# Sheet1.net
KiCad netlist of a schematic drawn in Altium Designer
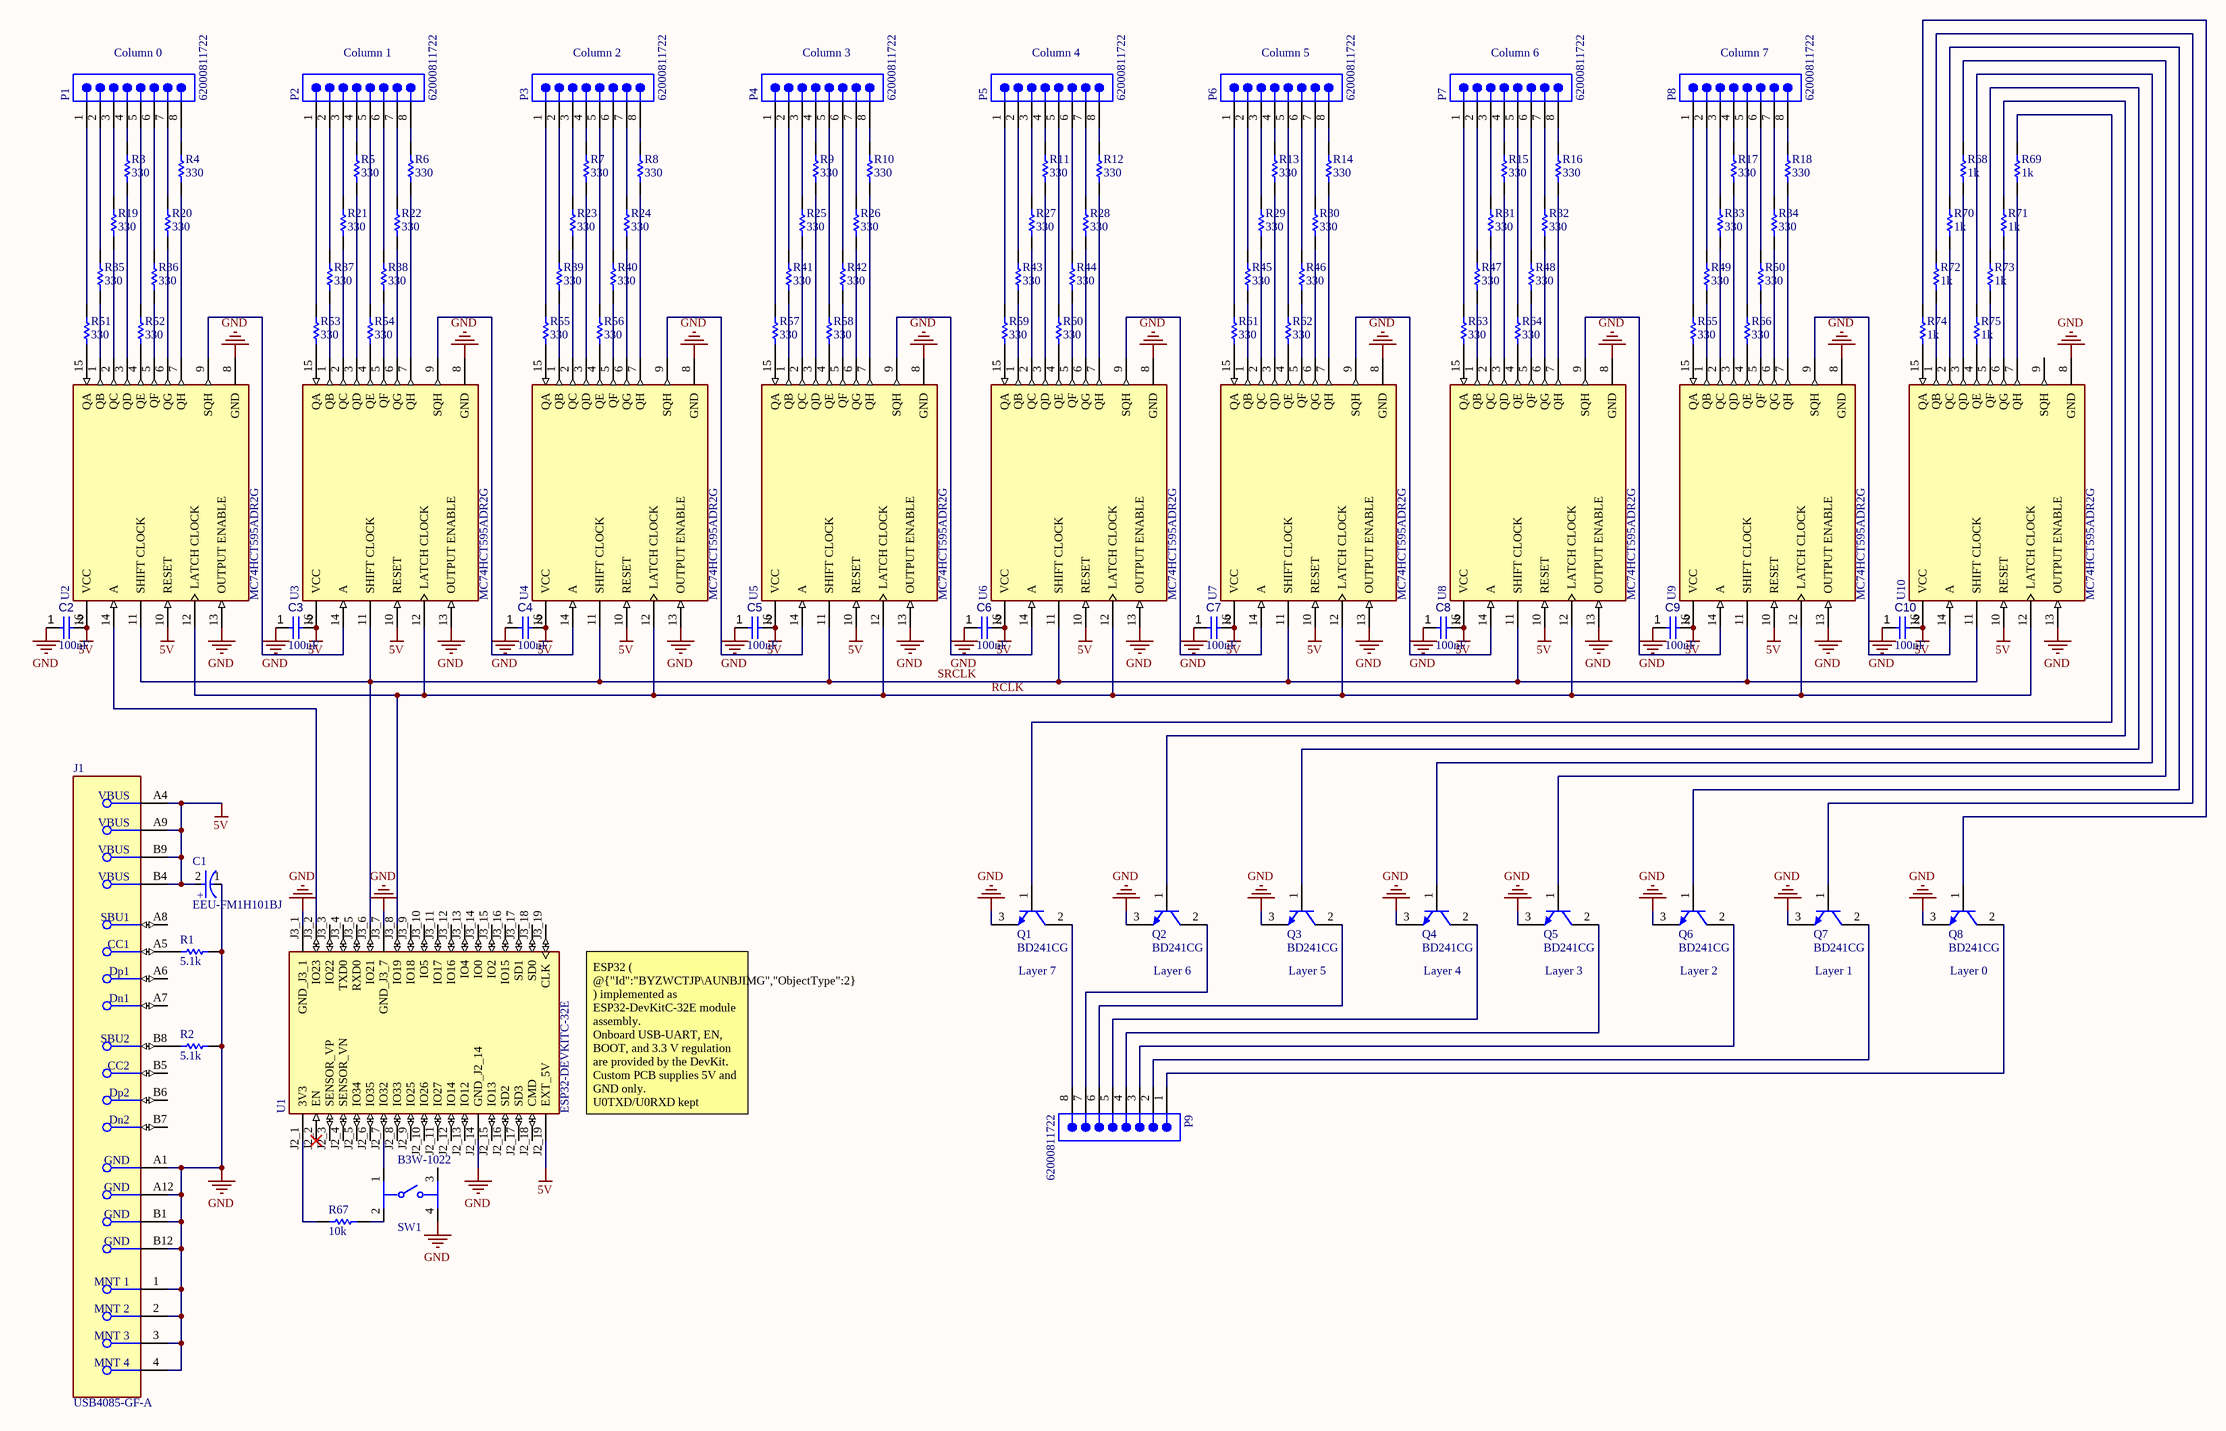
[diagram p0: Sheet1.SchDoc]

(export (version "E")
  (design (tool "Eeschema 10.0.6"))
  (components
    (comp (ref "C1")
      (value "EEU-FM1H101BJ")
      (footprint "FP-FM8-MFG")
      (description "CAP ALUM 100UF 20% 50V RADIAL")
      (fields (field (name "TOLERANCE") "20%"))
      (libsource (lib "Altium Content Vault") (part "203bc49f2ac43e59fd269a8c329ed05"))
    )
    (comp (ref "C2")
      (value "100nF")
      (footprint "CAPC0402(1005)60_L")
      (description "Chip Capacitor, 100nF +/-20%, 25V, 0402, Thickness 0.6 mm")
      (fields (field (name "TOLERANCE") "10%") (field (name "Comment") "Capacitor 100nF +/-20% 25V 0402"))
      (libsource (lib "nikita juscenko") (part "CAP-NP-2"))
    )
    (comp (ref "C3")
      (value "100nF")
      (footprint "CAPC0402(1005)60_L")
      (description "Chip Capacitor, 100nF +/-20%, 25V, 0402, Thickness 0.6 mm")
      (fields (field (name "TOLERANCE") "10%") (field (name "Comment") "Capacitor 100nF +/-20% 25V 0402"))
      (libsource (lib "nikita juscenko") (part "CAP-NP-2"))
    )
    (comp (ref "C4")
      (value "100nF")
      (footprint "CAPC0402(1005)60_L")
      (description "Chip Capacitor, 100nF +/-20%, 25V, 0402, Thickness 0.6 mm")
      (fields (field (name "TOLERANCE") "10%") (field (name "Comment") "Capacitor 100nF +/-20% 25V 0402"))
      (libsource (lib "nikita juscenko") (part "CAP-NP-2"))
    )
    (comp (ref "C5")
      (value "100nF")
      (footprint "CAPC0402(1005)60_L")
      (description "Chip Capacitor, 100nF +/-20%, 25V, 0402, Thickness 0.6 mm")
      (fields (field (name "TOLERANCE") "10%") (field (name "Comment") "Capacitor 100nF +/-20% 25V 0402"))
      (libsource (lib "nikita juscenko") (part "CAP-NP-2"))
    )
    (comp (ref "C6")
      (value "100nF")
      (footprint "CAPC0402(1005)60_L")
      (description "Chip Capacitor, 100nF +/-20%, 25V, 0402, Thickness 0.6 mm")
      (fields (field (name "TOLERANCE") "10%") (field (name "Comment") "Capacitor 100nF +/-20% 25V 0402"))
      (libsource (lib "nikita juscenko") (part "CAP-NP-2"))
    )
    (comp (ref "C7")
      (value "100nF")
      (footprint "CAPC0402(1005)60_L")
      (description "Chip Capacitor, 100nF +/-20%, 25V, 0402, Thickness 0.6 mm")
      (fields (field (name "TOLERANCE") "10%") (field (name "Comment") "Capacitor 100nF +/-20% 25V 0402"))
      (libsource (lib "nikita juscenko") (part "CAP-NP-2"))
    )
    (comp (ref "C8")
      (value "100nF")
      (footprint "CAPC0402(1005)60_L")
      (description "Chip Capacitor, 100nF +/-20%, 25V, 0402, Thickness 0.6 mm")
      (fields (field (name "TOLERANCE") "10%") (field (name "Comment") "Capacitor 100nF +/-20% 25V 0402"))
      (libsource (lib "nikita juscenko") (part "CAP-NP-2"))
    )
    (comp (ref "C9")
      (value "100nF")
      (footprint "CAPC0402(1005)60_L")
      (description "Chip Capacitor, 100nF +/-20%, 25V, 0402, Thickness 0.6 mm")
      (fields (field (name "TOLERANCE") "10%") (field (name "Comment") "Capacitor 100nF +/-20% 25V 0402"))
      (libsource (lib "nikita juscenko") (part "CAP-NP-2"))
    )
    (comp (ref "C10")
      (value "100nF")
      (footprint "CAPC0402(1005)60_L")
      (description "Chip Capacitor, 100nF +/-20%, 25V, 0402, Thickness 0.6 mm")
      (fields (field (name "TOLERANCE") "10%") (field (name "Comment") "Capacitor 100nF +/-20% 25V 0402"))
      (libsource (lib "nikita juscenko") (part "CAP-NP-2"))
    )
    (comp (ref "J1")
      (value "USB4085-GF-A")
      (footprint "FP-USB4085-GF-A-MFG")
      (description "CONN RCPT USB2.0 TYPE C 24POS RA")
      (libsource (lib "Altium Content Vault") (part "10fa745527c8b974685cbca3c197132"))
    )
    (comp (ref "P1")
      (value "62000811722")
      (footprint "62000811722")
      (description "WR-WTB Wire-to-Board Connectors 2.00 mm")
      (libsource (lib "Altium Content Vault") (part "Header_Male_1R_08P"))
    )
    (comp (ref "P2")
      (value "62000811722")
      (footprint "62000811722")
      (description "WR-WTB Wire-to-Board Connectors 2.00 mm")
      (libsource (lib "Altium Content Vault") (part "Header_Male_1R_08P"))
    )
    (comp (ref "P3")
      (value "62000811722")
      (footprint "62000811722")
      (description "WR-WTB Wire-to-Board Connectors 2.00 mm")
      (libsource (lib "Altium Content Vault") (part "Header_Male_1R_08P"))
    )
    (comp (ref "P4")
      (value "62000811722")
      (footprint "62000811722")
      (description "WR-WTB Wire-to-Board Connectors 2.00 mm")
      (libsource (lib "Altium Content Vault") (part "Header_Male_1R_08P"))
    )
    (comp (ref "P5")
      (value "62000811722")
      (footprint "62000811722")
      (description "WR-WTB Wire-to-Board Connectors 2.00 mm")
      (libsource (lib "Altium Content Vault") (part "Header_Male_1R_08P"))
    )
    (comp (ref "P6")
      (value "62000811722")
      (footprint "62000811722")
      (description "WR-WTB Wire-to-Board Connectors 2.00 mm")
      (libsource (lib "Altium Content Vault") (part "Header_Male_1R_08P"))
    )
    (comp (ref "P7")
      (value "62000811722")
      (footprint "62000811722")
      (description "WR-WTB Wire-to-Board Connectors 2.00 mm")
      (libsource (lib "Altium Content Vault") (part "Header_Male_1R_08P"))
    )
    (comp (ref "P8")
      (value "62000811722")
      (footprint "62000811722")
      (description "WR-WTB Wire-to-Board Connectors 2.00 mm")
      (libsource (lib "Altium Content Vault") (part "Header_Male_1R_08P"))
    )
    (comp (ref "P9")
      (value "62000811722")
      (footprint "62000811722")
      (description "WR-WTB Wire-to-Board Connectors 2.00 mm")
      (libsource (lib "Altium Content Vault") (part "Header_Male_1R_08P"))
    )
    (comp (ref "Q1")
      (value "BD241CG")
      (footprint "ONSC-TO-220-3-221A-09")
      (description "Complementary Silicon Plastic Power Transistor, 3-Pin TO-220, Pb-Free, Tube")
      (fields (field (name "MANUFACTURER") "On Semiconductor"))
      (libsource (lib "Altium Content Vault") (part "ONSC-NPN-B1C2E3-3_C"))
    )
    (comp (ref "Q2")
      (value "BD241CG")
      (footprint "ONSC-TO-220-3-221A-09")
      (description "Complementary Silicon Plastic Power Transistor, 3-Pin TO-220, Pb-Free, Tube")
      (fields (field (name "MANUFACTURER") "On Semiconductor"))
      (libsource (lib "Altium Content Vault") (part "ONSC-NPN-B1C2E3-3_C"))
    )
    (comp (ref "Q3")
      (value "BD241CG")
      (footprint "ONSC-TO-220-3-221A-09")
      (description "Complementary Silicon Plastic Power Transistor, 3-Pin TO-220, Pb-Free, Tube")
      (fields (field (name "MANUFACTURER") "On Semiconductor"))
      (libsource (lib "Altium Content Vault") (part "ONSC-NPN-B1C2E3-3_C"))
    )
    (comp (ref "Q4")
      (value "BD241CG")
      (footprint "ONSC-TO-220-3-221A-09")
      (description "Complementary Silicon Plastic Power Transistor, 3-Pin TO-220, Pb-Free, Tube")
      (fields (field (name "MANUFACTURER") "On Semiconductor"))
      (libsource (lib "Altium Content Vault") (part "ONSC-NPN-B1C2E3-3_C"))
    )
    (comp (ref "Q5")
      (value "BD241CG")
      (footprint "ONSC-TO-220-3-221A-09")
      (description "Complementary Silicon Plastic Power Transistor, 3-Pin TO-220, Pb-Free, Tube")
      (fields (field (name "MANUFACTURER") "On Semiconductor"))
      (libsource (lib "Altium Content Vault") (part "ONSC-NPN-B1C2E3-3_C"))
    )
    (comp (ref "Q6")
      (value "BD241CG")
      (footprint "ONSC-TO-220-3-221A-09")
      (description "Complementary Silicon Plastic Power Transistor, 3-Pin TO-220, Pb-Free, Tube")
      (fields (field (name "MANUFACTURER") "On Semiconductor"))
      (libsource (lib "Altium Content Vault") (part "ONSC-NPN-B1C2E3-3_C"))
    )
    (comp (ref "Q7")
      (value "BD241CG")
      (footprint "ONSC-TO-220-3-221A-09")
      (description "Complementary Silicon Plastic Power Transistor, 3-Pin TO-220, Pb-Free, Tube")
      (fields (field (name "MANUFACTURER") "On Semiconductor"))
      (libsource (lib "Altium Content Vault") (part "ONSC-NPN-B1C2E3-3_C"))
    )
    (comp (ref "Q8")
      (value "BD241CG")
      (footprint "ONSC-TO-220-3-221A-09")
      (description "Complementary Silicon Plastic Power Transistor, 3-Pin TO-220, Pb-Free, Tube")
      (fields (field (name "MANUFACTURER") "On Semiconductor"))
      (libsource (lib "Altium Content Vault") (part "ONSC-NPN-B1C2E3-3_C"))
    )
    (comp (ref "R1")
      (value "5.1k")
      (description "Resistor")
      (libsource (lib "Simulation Generic Components") (part "Resistor"))
    )
    (comp (ref "R2")
      (value "5.1k")
      (description "Resistor")
      (libsource (lib "Simulation Generic Components") (part "Resistor"))
    )
    (comp (ref "R3")
      (value "330")
      (description "Resistor")
      (libsource (lib "Simulation Generic Components") (part "Resistor"))
    )
    (comp (ref "R4")
      (value "330")
      (description "Resistor")
      (libsource (lib "Simulation Generic Components") (part "Resistor"))
    )
    (comp (ref "R5")
      (value "330")
      (description "Resistor")
      (libsource (lib "Simulation Generic Components") (part "Resistor"))
    )
    (comp (ref "R6")
      (value "330")
      (description "Resistor")
      (libsource (lib "Simulation Generic Components") (part "Resistor"))
    )
    (comp (ref "R7")
      (value "330")
      (description "Resistor")
      (libsource (lib "Simulation Generic Components") (part "Resistor"))
    )
    (comp (ref "R8")
      (value "330")
      (description "Resistor")
      (libsource (lib "Simulation Generic Components") (part "Resistor"))
    )
    (comp (ref "R9")
      (value "330")
      (description "Resistor")
      (libsource (lib "Simulation Generic Components") (part "Resistor"))
    )
    (comp (ref "R10")
      (value "330")
      (description "Resistor")
      (libsource (lib "Simulation Generic Components") (part "Resistor"))
    )
    (comp (ref "R11")
      (value "330")
      (description "Resistor")
      (libsource (lib "Simulation Generic Components") (part "Resistor"))
    )
    (comp (ref "R12")
      (value "330")
      (description "Resistor")
      (libsource (lib "Simulation Generic Components") (part "Resistor"))
    )
    (comp (ref "R13")
      (value "330")
      (description "Resistor")
      (libsource (lib "Simulation Generic Components") (part "Resistor"))
    )
    (comp (ref "R14")
      (value "330")
      (description "Resistor")
      (libsource (lib "Simulation Generic Components") (part "Resistor"))
    )
    (comp (ref "R15")
      (value "330")
      (description "Resistor")
      (libsource (lib "Simulation Generic Components") (part "Resistor"))
    )
    (comp (ref "R16")
      (value "330")
      (description "Resistor")
      (libsource (lib "Simulation Generic Components") (part "Resistor"))
    )
    (comp (ref "R17")
      (value "330")
      (description "Resistor")
      (libsource (lib "Simulation Generic Components") (part "Resistor"))
    )
    (comp (ref "R18")
      (value "330")
      (description "Resistor")
      (libsource (lib "Simulation Generic Components") (part "Resistor"))
    )
    (comp (ref "R19")
      (value "330")
      (description "Resistor")
      (libsource (lib "Simulation Generic Components") (part "Resistor"))
    )
    (comp (ref "R20")
      (value "330")
      (description "Resistor")
      (libsource (lib "Simulation Generic Components") (part "Resistor"))
    )
    (comp (ref "R21")
      (value "330")
      (description "Resistor")
      (libsource (lib "Simulation Generic Components") (part "Resistor"))
    )
    (comp (ref "R22")
      (value "330")
      (description "Resistor")
      (libsource (lib "Simulation Generic Components") (part "Resistor"))
    )
    (comp (ref "R23")
      (value "330")
      (description "Resistor")
      (libsource (lib "Simulation Generic Components") (part "Resistor"))
    )
    (comp (ref "R24")
      (value "330")
      (description "Resistor")
      (libsource (lib "Simulation Generic Components") (part "Resistor"))
    )
    (comp (ref "R25")
      (value "330")
      (description "Resistor")
      (libsource (lib "Simulation Generic Components") (part "Resistor"))
    )
    (comp (ref "R26")
      (value "330")
      (description "Resistor")
      (libsource (lib "Simulation Generic Components") (part "Resistor"))
    )
    (comp (ref "R27")
      (value "330")
      (description "Resistor")
      (libsource (lib "Simulation Generic Components") (part "Resistor"))
    )
    (comp (ref "R28")
      (value "330")
      (description "Resistor")
      (libsource (lib "Simulation Generic Components") (part "Resistor"))
    )
    (comp (ref "R29")
      (value "330")
      (description "Resistor")
      (libsource (lib "Simulation Generic Components") (part "Resistor"))
    )
    (comp (ref "R30")
      (value "330")
      (description "Resistor")
      (libsource (lib "Simulation Generic Components") (part "Resistor"))
    )
    (comp (ref "R31")
      (value "330")
      (description "Resistor")
      (libsource (lib "Simulation Generic Components") (part "Resistor"))
    )
    (comp (ref "R32")
      (value "330")
      (description "Resistor")
      (libsource (lib "Simulation Generic Components") (part "Resistor"))
    )
    (comp (ref "R33")
      (value "330")
      (description "Resistor")
      (libsource (lib "Simulation Generic Components") (part "Resistor"))
    )
    (comp (ref "R34")
      (value "330")
      (description "Resistor")
      (libsource (lib "Simulation Generic Components") (part "Resistor"))
    )
    (comp (ref "R35")
      (value "330")
      (description "Resistor")
      (libsource (lib "Simulation Generic Components") (part "Resistor"))
    )
    (comp (ref "R36")
      (value "330")
      (description "Resistor")
      (libsource (lib "Simulation Generic Components") (part "Resistor"))
    )
    (comp (ref "R37")
      (value "330")
      (description "Resistor")
      (libsource (lib "Simulation Generic Components") (part "Resistor"))
    )
    (comp (ref "R38")
      (value "330")
      (description "Resistor")
      (libsource (lib "Simulation Generic Components") (part "Resistor"))
    )
    (comp (ref "R39")
      (value "330")
      (description "Resistor")
      (libsource (lib "Simulation Generic Components") (part "Resistor"))
    )
    (comp (ref "R40")
      (value "330")
      (description "Resistor")
      (libsource (lib "Simulation Generic Components") (part "Resistor"))
    )
    (comp (ref "R41")
      (value "330")
      (description "Resistor")
      (libsource (lib "Simulation Generic Components") (part "Resistor"))
    )
    (comp (ref "R42")
      (value "330")
      (description "Resistor")
      (libsource (lib "Simulation Generic Components") (part "Resistor"))
    )
    (comp (ref "R43")
      (value "330")
      (description "Resistor")
      (libsource (lib "Simulation Generic Components") (part "Resistor"))
    )
    (comp (ref "R44")
      (value "330")
      (description "Resistor")
      (libsource (lib "Simulation Generic Components") (part "Resistor"))
    )
    (comp (ref "R45")
      (value "330")
      (description "Resistor")
      (libsource (lib "Simulation Generic Components") (part "Resistor"))
    )
    (comp (ref "R46")
      (value "330")
      (description "Resistor")
      (libsource (lib "Simulation Generic Components") (part "Resistor"))
    )
    (comp (ref "R47")
      (value "330")
      (description "Resistor")
      (libsource (lib "Simulation Generic Components") (part "Resistor"))
    )
    (comp (ref "R48")
      (value "330")
      (description "Resistor")
      (libsource (lib "Simulation Generic Components") (part "Resistor"))
    )
    (comp (ref "R49")
      (value "330")
      (description "Resistor")
      (libsource (lib "Simulation Generic Components") (part "Resistor"))
    )
    (comp (ref "R50")
      (value "330")
      (description "Resistor")
      (libsource (lib "Simulation Generic Components") (part "Resistor"))
    )
    (comp (ref "R51")
      (value "330")
      (description "Resistor")
      (libsource (lib "Simulation Generic Components") (part "Resistor"))
    )
    (comp (ref "R52")
      (value "330")
      (description "Resistor")
      (libsource (lib "Simulation Generic Components") (part "Resistor"))
    )
    (comp (ref "R53")
      (value "330")
      (description "Resistor")
      (libsource (lib "Simulation Generic Components") (part "Resistor"))
    )
    (comp (ref "R54")
      (value "330")
      (description "Resistor")
      (libsource (lib "Simulation Generic Components") (part "Resistor"))
    )
    (comp (ref "R55")
      (value "330")
      (description "Resistor")
      (libsource (lib "Simulation Generic Components") (part "Resistor"))
    )
    (comp (ref "R56")
      (value "330")
      (description "Resistor")
      (libsource (lib "Simulation Generic Components") (part "Resistor"))
    )
    (comp (ref "R57")
      (value "330")
      (description "Resistor")
      (libsource (lib "Simulation Generic Components") (part "Resistor"))
    )
    (comp (ref "R58")
      (value "330")
      (description "Resistor")
      (libsource (lib "Simulation Generic Components") (part "Resistor"))
    )
    (comp (ref "R59")
      (value "330")
      (description "Resistor")
      (libsource (lib "Simulation Generic Components") (part "Resistor"))
    )
    (comp (ref "R60")
      (value "330")
      (description "Resistor")
      (libsource (lib "Simulation Generic Components") (part "Resistor"))
    )
    (comp (ref "R61")
      (value "330")
      (description "Resistor")
      (libsource (lib "Simulation Generic Components") (part "Resistor"))
    )
    (comp (ref "R62")
      (value "330")
      (description "Resistor")
      (libsource (lib "Simulation Generic Components") (part "Resistor"))
    )
    (comp (ref "R63")
      (value "330")
      (description "Resistor")
      (libsource (lib "Simulation Generic Components") (part "Resistor"))
    )
    (comp (ref "R64")
      (value "330")
      (description "Resistor")
      (libsource (lib "Simulation Generic Components") (part "Resistor"))
    )
    (comp (ref "R65")
      (value "330")
      (description "Resistor")
      (libsource (lib "Simulation Generic Components") (part "Resistor"))
    )
    (comp (ref "R66")
      (value "330")
      (description "Resistor")
      (libsource (lib "Simulation Generic Components") (part "Resistor"))
    )
    (comp (ref "R67")
      (value "10k")
      (description "Resistor")
      (libsource (lib "Simulation Generic Components") (part "Resistor"))
    )
    (comp (ref "R68")
      (value "1k")
      (description "Resistor")
      (libsource (lib "Simulation Generic Components") (part "Resistor"))
    )
    (comp (ref "R69")
      (value "1k")
      (description "Resistor")
      (libsource (lib "Simulation Generic Components") (part "Resistor"))
    )
    (comp (ref "R70")
      (value "1k")
      (description "Resistor")
      (libsource (lib "Simulation Generic Components") (part "Resistor"))
    )
    (comp (ref "R71")
      (value "1k")
      (description "Resistor")
      (libsource (lib "Simulation Generic Components") (part "Resistor"))
    )
    (comp (ref "R72")
      (value "1k")
      (description "Resistor")
      (libsource (lib "Simulation Generic Components") (part "Resistor"))
    )
    (comp (ref "R73")
      (value "1k")
      (description "Resistor")
      (libsource (lib "Simulation Generic Components") (part "Resistor"))
    )
    (comp (ref "R74")
      (value "1k")
      (description "Resistor")
      (libsource (lib "Simulation Generic Components") (part "Resistor"))
    )
    (comp (ref "R75")
      (value "1k")
      (description "Resistor")
      (libsource (lib "Simulation Generic Components") (part "Resistor"))
    )
    (comp (ref "SW1")
      (value "B3W-1022")
      (footprint "FP-B3W-1022-MFG")
      (description "SWITCH TACTILE SPST-NO 0.05A 24V")
      (libsource (lib "Altium Content Vault") (part "b8895f3f4cefb76e1819d2863dba89b"))
    )
    (comp (ref "U1")
      (value "ESP32-DEVKITC-32E")
      (footprint "MODULE_ESP32-DEVKITC-32E")
      (description "ESP32-WROOM-32E Series Evaluation Board 802.11 b/g/n (WiFi, WLAN) Bluetooth Smart Ready 4.x")
      (fields (field (name "MF") "Espressif Systems"))
      (libsource (lib "nikita juscenko") (part "ESP32-DEVKITC-32E"))
    )
    (comp (ref "U2")
      (value "MC74HCT595ADR2G")
      (footprint "FP-751B-05-MFG")
      (libsource (lib "Altium Content Vault") (part "355c601ec69527b18b491ba11f96b67"))
    )
    (comp (ref "U3")
      (value "MC74HCT595ADR2G")
      (footprint "FP-751B-05-MFG")
      (libsource (lib "Altium Content Vault") (part "355c601ec69527b18b491ba11f96b67"))
    )
    (comp (ref "U4")
      (value "MC74HCT595ADR2G")
      (footprint "FP-751B-05-MFG")
      (libsource (lib "Altium Content Vault") (part "355c601ec69527b18b491ba11f96b67"))
    )
    (comp (ref "U5")
      (value "MC74HCT595ADR2G")
      (footprint "FP-751B-05-MFG")
      (libsource (lib "Altium Content Vault") (part "355c601ec69527b18b491ba11f96b67"))
    )
    (comp (ref "U6")
      (value "MC74HCT595ADR2G")
      (footprint "FP-751B-05-MFG")
      (libsource (lib "Altium Content Vault") (part "355c601ec69527b18b491ba11f96b67"))
    )
    (comp (ref "U7")
      (value "MC74HCT595ADR2G")
      (footprint "FP-751B-05-MFG")
      (libsource (lib "Altium Content Vault") (part "355c601ec69527b18b491ba11f96b67"))
    )
    (comp (ref "U8")
      (value "MC74HCT595ADR2G")
      (footprint "FP-751B-05-MFG")
      (libsource (lib "Altium Content Vault") (part "355c601ec69527b18b491ba11f96b67"))
    )
    (comp (ref "U9")
      (value "MC74HCT595ADR2G")
      (footprint "FP-751B-05-MFG")
      (libsource (lib "Altium Content Vault") (part "355c601ec69527b18b491ba11f96b67"))
    )
    (comp (ref "U10")
      (value "MC74HCT595ADR2G")
      (footprint "FP-751B-05-MFG")
      (libsource (lib "Altium Content Vault") (part "355c601ec69527b18b491ba11f96b67"))
    )
  )
  (nets
    (net (code "1") (name "/RCLK") (class "Default")
      (node (ref "U1") (pin "J3_8") (pinfunction "IO19_J3_8") (pintype "bidirectional"))
      (node (ref "U10") (pin "12") (pinfunction "LATCH_CLOCK_12") (pintype "passive"))
      (node (ref "U2") (pin "12") (pinfunction "LATCH_CLOCK_12") (pintype "passive"))
      (node (ref "U3") (pin "12") (pinfunction "LATCH_CLOCK_12") (pintype "passive"))
      (node (ref "U4") (pin "12") (pinfunction "LATCH_CLOCK_12") (pintype "passive"))
      (node (ref "U5") (pin "12") (pinfunction "LATCH_CLOCK_12") (pintype "passive"))
      (node (ref "U6") (pin "12") (pinfunction "LATCH_CLOCK_12") (pintype "passive"))
      (node (ref "U7") (pin "12") (pinfunction "LATCH_CLOCK_12") (pintype "passive"))
      (node (ref "U8") (pin "12") (pinfunction "LATCH_CLOCK_12") (pintype "passive"))
      (node (ref "U9") (pin "12") (pinfunction "LATCH_CLOCK_12") (pintype "passive"))
    )
    (net (code "2") (name "/SRCLK") (class "Default")
      (node (ref "U1") (pin "J3_6") (pinfunction "IO21_J3_6") (pintype "bidirectional"))
      (node (ref "U10") (pin "11") (pinfunction "SHIFT_CLOCK_11") (pintype "passive"))
      (node (ref "U2") (pin "11") (pinfunction "SHIFT_CLOCK_11") (pintype "passive"))
      (node (ref "U3") (pin "11") (pinfunction "SHIFT_CLOCK_11") (pintype "passive"))
      (node (ref "U4") (pin "11") (pinfunction "SHIFT_CLOCK_11") (pintype "passive"))
      (node (ref "U5") (pin "11") (pinfunction "SHIFT_CLOCK_11") (pintype "passive"))
      (node (ref "U6") (pin "11") (pinfunction "SHIFT_CLOCK_11") (pintype "passive"))
      (node (ref "U7") (pin "11") (pinfunction "SHIFT_CLOCK_11") (pintype "passive"))
      (node (ref "U8") (pin "11") (pinfunction "SHIFT_CLOCK_11") (pintype "passive"))
      (node (ref "U9") (pin "11") (pinfunction "SHIFT_CLOCK_11") (pintype "passive"))
    )
    (net (code "3") (name "5V") (class "Default")
      (node (ref "C1") (pin "2") (pinfunction "A_2") (pintype "passive"))
      (node (ref "C10") (pin "2") (pinfunction "2_2") (pintype "passive"))
      (node (ref "C2") (pin "2") (pinfunction "2_2") (pintype "passive"))
      (node (ref "C3") (pin "2") (pinfunction "2_2") (pintype "passive"))
      (node (ref "C4") (pin "2") (pinfunction "2_2") (pintype "passive"))
      (node (ref "C5") (pin "2") (pinfunction "2_2") (pintype "passive"))
      (node (ref "C6") (pin "2") (pinfunction "2_2") (pintype "passive"))
      (node (ref "C7") (pin "2") (pinfunction "2_2") (pintype "passive"))
      (node (ref "C8") (pin "2") (pinfunction "2_2") (pintype "passive"))
      (node (ref "C9") (pin "2") (pinfunction "2_2") (pintype "passive"))
      (node (ref "J1") (pin "A4") (pinfunction "VBUS_A4") (pintype "power_in"))
      (node (ref "J1") (pin "A9") (pinfunction "VBUS_A9") (pintype "power_in"))
      (node (ref "J1") (pin "B4") (pinfunction "VBUS_B4") (pintype "power_in"))
      (node (ref "J1") (pin "B9") (pinfunction "VBUS_B9") (pintype "power_in"))
      (node (ref "U1") (pin "J2_19") (pinfunction "EXT_5V_J2_19") (pintype "power_in"))
      (node (ref "U10") (pin "10") (pinfunction "RESET_10") (pintype "input"))
      (node (ref "U10") (pin "16") (pinfunction "VCC_16") (pintype "power_in"))
      (node (ref "U2") (pin "10") (pinfunction "RESET_10") (pintype "input"))
      (node (ref "U2") (pin "16") (pinfunction "VCC_16") (pintype "power_in"))
      (node (ref "U3") (pin "10") (pinfunction "RESET_10") (pintype "input"))
      (node (ref "U3") (pin "16") (pinfunction "VCC_16") (pintype "power_in"))
      (node (ref "U4") (pin "10") (pinfunction "RESET_10") (pintype "input"))
      (node (ref "U4") (pin "16") (pinfunction "VCC_16") (pintype "power_in"))
      (node (ref "U5") (pin "10") (pinfunction "RESET_10") (pintype "input"))
      (node (ref "U5") (pin "16") (pinfunction "VCC_16") (pintype "power_in"))
      (node (ref "U6") (pin "10") (pinfunction "RESET_10") (pintype "input"))
      (node (ref "U6") (pin "16") (pinfunction "VCC_16") (pintype "power_in"))
      (node (ref "U7") (pin "10") (pinfunction "RESET_10") (pintype "input"))
      (node (ref "U7") (pin "16") (pinfunction "VCC_16") (pintype "power_in"))
      (node (ref "U8") (pin "10") (pinfunction "RESET_10") (pintype "input"))
      (node (ref "U8") (pin "16") (pinfunction "VCC_16") (pintype "power_in"))
      (node (ref "U9") (pin "10") (pinfunction "RESET_10") (pintype "input"))
      (node (ref "U9") (pin "16") (pinfunction "VCC_16") (pintype "power_in"))
    )
    (net (code "4") (name "GND") (class "Default")
      (node (ref "C1") (pin "1") (pinfunction "C_1") (pintype "passive"))
      (node (ref "C10") (pin "1") (pinfunction "1_1") (pintype "passive"))
      (node (ref "C2") (pin "1") (pinfunction "1_1") (pintype "passive"))
      (node (ref "C3") (pin "1") (pinfunction "1_1") (pintype "passive"))
      (node (ref "C4") (pin "1") (pinfunction "1_1") (pintype "passive"))
      (node (ref "C5") (pin "1") (pinfunction "1_1") (pintype "passive"))
      (node (ref "C6") (pin "1") (pinfunction "1_1") (pintype "passive"))
      (node (ref "C7") (pin "1") (pinfunction "1_1") (pintype "passive"))
      (node (ref "C8") (pin "1") (pinfunction "1_1") (pintype "passive"))
      (node (ref "C9") (pin "1") (pinfunction "1_1") (pintype "passive"))
      (node (ref "J1") (pin "1") (pinfunction "MNT_1_1") (pintype "passive"))
      (node (ref "J1") (pin "2") (pinfunction "MNT_2_2") (pintype "passive"))
      (node (ref "J1") (pin "3") (pinfunction "MNT_3_3") (pintype "passive"))
      (node (ref "J1") (pin "4") (pinfunction "MNT_4_4") (pintype "passive"))
      (node (ref "J1") (pin "A1") (pinfunction "GND_A1") (pintype "power_in"))
      (node (ref "J1") (pin "A12") (pinfunction "GND_A12") (pintype "power_in"))
      (node (ref "J1") (pin "B1") (pinfunction "GND_B1") (pintype "power_in"))
      (node (ref "J1") (pin "B12") (pinfunction "GND_B12") (pintype "power_in"))
      (node (ref "Q1") (pin "3") (pinfunction "E_3") (pintype "passive"))
      (node (ref "Q2") (pin "3") (pinfunction "E_3") (pintype "passive"))
      (node (ref "Q3") (pin "3") (pinfunction "E_3") (pintype "passive"))
      (node (ref "Q4") (pin "3") (pinfunction "E_3") (pintype "passive"))
      (node (ref "Q5") (pin "3") (pinfunction "E_3") (pintype "passive"))
      (node (ref "Q6") (pin "3") (pinfunction "E_3") (pintype "passive"))
      (node (ref "Q7") (pin "3") (pinfunction "E_3") (pintype "passive"))
      (node (ref "Q8") (pin "3") (pinfunction "E_3") (pintype "passive"))
      (node (ref "R1") (pin "2") (pinfunction "2_2") (pintype "passive"))
      (node (ref "R2") (pin "2") (pinfunction "2_2") (pintype "passive"))
      (node (ref "SW1") (pin "4") (pinfunction "4_4") (pintype "passive"))
      (node (ref "U1") (pin "J2_14") (pinfunction "GND_J2_14_J2_14") (pintype "power_in"))
      (node (ref "U1") (pin "J3_1") (pinfunction "GND_J3_1_J3_1") (pintype "power_in"))
      (node (ref "U1") (pin "J3_7") (pinfunction "GND_J3_7_J3_7") (pintype "power_in"))
      (node (ref "U10") (pin "13") (pinfunction "OUTPUT_ENABLE_13") (pintype "input"))
      (node (ref "U10") (pin "8") (pinfunction "GND_8") (pintype "power_in"))
      (node (ref "U2") (pin "13") (pinfunction "OUTPUT_ENABLE_13") (pintype "input"))
      (node (ref "U2") (pin "8") (pinfunction "GND_8") (pintype "power_in"))
      (node (ref "U3") (pin "13") (pinfunction "OUTPUT_ENABLE_13") (pintype "input"))
      (node (ref "U3") (pin "8") (pinfunction "GND_8") (pintype "power_in"))
      (node (ref "U4") (pin "13") (pinfunction "OUTPUT_ENABLE_13") (pintype "input"))
      (node (ref "U4") (pin "8") (pinfunction "GND_8") (pintype "power_in"))
      (node (ref "U5") (pin "13") (pinfunction "OUTPUT_ENABLE_13") (pintype "input"))
      (node (ref "U5") (pin "8") (pinfunction "GND_8") (pintype "power_in"))
      (node (ref "U6") (pin "13") (pinfunction "OUTPUT_ENABLE_13") (pintype "input"))
      (node (ref "U6") (pin "8") (pinfunction "GND_8") (pintype "power_in"))
      (node (ref "U7") (pin "13") (pinfunction "OUTPUT_ENABLE_13") (pintype "input"))
      (node (ref "U7") (pin "8") (pinfunction "GND_8") (pintype "power_in"))
      (node (ref "U8") (pin "13") (pinfunction "OUTPUT_ENABLE_13") (pintype "input"))
      (node (ref "U8") (pin "8") (pinfunction "GND_8") (pintype "power_in"))
      (node (ref "U9") (pin "13") (pinfunction "OUTPUT_ENABLE_13") (pintype "input"))
      (node (ref "U9") (pin "8") (pinfunction "GND_8") (pintype "power_in"))
    )
    (net (code "5") (name "Net-(J1-CC1)") (class "Default")
      (node (ref "J1") (pin "A5") (pinfunction "CC1_A5") (pintype "bidirectional"))
      (node (ref "R1") (pin "1") (pinfunction "1_1") (pintype "passive"))
    )
    (net (code "6") (name "Net-(J1-SBU2)") (class "Default")
      (node (ref "J1") (pin "B8") (pinfunction "SBU2_B8") (pintype "bidirectional"))
      (node (ref "R2") (pin "1") (pinfunction "1_1") (pintype "passive"))
    )
    (net (code "7") (name "Net-(P1-Pad1)") (class "Default")
      (node (ref "P1") (pin "1") (pinfunction "1_1") (pintype "passive"))
      (node (ref "R51") (pin "2") (pinfunction "2_2") (pintype "passive"))
    )
    (net (code "8") (name "Net-(P1-Pad2)") (class "Default")
      (node (ref "P1") (pin "2") (pinfunction "2_2") (pintype "passive"))
      (node (ref "R35") (pin "2") (pinfunction "2_2") (pintype "passive"))
    )
    (net (code "9") (name "Net-(P1-Pad3)") (class "Default")
      (node (ref "P1") (pin "3") (pinfunction "3_3") (pintype "passive"))
      (node (ref "R19") (pin "2") (pinfunction "2_2") (pintype "passive"))
    )
    (net (code "10") (name "Net-(P1-Pad4)") (class "Default")
      (node (ref "P1") (pin "4") (pinfunction "4_4") (pintype "passive"))
      (node (ref "R3") (pin "2") (pinfunction "2_2") (pintype "passive"))
    )
    (net (code "11") (name "Net-(P1-Pad5)") (class "Default")
      (node (ref "P1") (pin "5") (pinfunction "5_5") (pintype "passive"))
      (node (ref "R52") (pin "2") (pinfunction "2_2") (pintype "passive"))
    )
    (net (code "12") (name "Net-(P1-Pad6)") (class "Default")
      (node (ref "P1") (pin "6") (pinfunction "6_6") (pintype "passive"))
      (node (ref "R36") (pin "2") (pinfunction "2_2") (pintype "passive"))
    )
    (net (code "13") (name "Net-(P1-Pad7)") (class "Default")
      (node (ref "P1") (pin "7") (pinfunction "7_7") (pintype "passive"))
      (node (ref "R20") (pin "2") (pinfunction "2_2") (pintype "passive"))
    )
    (net (code "14") (name "Net-(P1-Pad8)") (class "Default")
      (node (ref "P1") (pin "8") (pinfunction "8_8") (pintype "passive"))
      (node (ref "R4") (pin "2") (pinfunction "2_2") (pintype "passive"))
    )
    (net (code "15") (name "Net-(P2-Pad1)") (class "Default")
      (node (ref "P2") (pin "1") (pinfunction "1_1") (pintype "passive"))
      (node (ref "R53") (pin "2") (pinfunction "2_2") (pintype "passive"))
    )
    (net (code "16") (name "Net-(P2-Pad2)") (class "Default")
      (node (ref "P2") (pin "2") (pinfunction "2_2") (pintype "passive"))
      (node (ref "R37") (pin "2") (pinfunction "2_2") (pintype "passive"))
    )
    (net (code "17") (name "Net-(P2-Pad3)") (class "Default")
      (node (ref "P2") (pin "3") (pinfunction "3_3") (pintype "passive"))
      (node (ref "R21") (pin "2") (pinfunction "2_2") (pintype "passive"))
    )
    (net (code "18") (name "Net-(P2-Pad4)") (class "Default")
      (node (ref "P2") (pin "4") (pinfunction "4_4") (pintype "passive"))
      (node (ref "R5") (pin "2") (pinfunction "2_2") (pintype "passive"))
    )
    (net (code "19") (name "Net-(P2-Pad5)") (class "Default")
      (node (ref "P2") (pin "5") (pinfunction "5_5") (pintype "passive"))
      (node (ref "R54") (pin "2") (pinfunction "2_2") (pintype "passive"))
    )
    (net (code "20") (name "Net-(P2-Pad6)") (class "Default")
      (node (ref "P2") (pin "6") (pinfunction "6_6") (pintype "passive"))
      (node (ref "R38") (pin "2") (pinfunction "2_2") (pintype "passive"))
    )
    (net (code "21") (name "Net-(P2-Pad7)") (class "Default")
      (node (ref "P2") (pin "7") (pinfunction "7_7") (pintype "passive"))
      (node (ref "R22") (pin "2") (pinfunction "2_2") (pintype "passive"))
    )
    (net (code "22") (name "Net-(P2-Pad8)") (class "Default")
      (node (ref "P2") (pin "8") (pinfunction "8_8") (pintype "passive"))
      (node (ref "R6") (pin "2") (pinfunction "2_2") (pintype "passive"))
    )
    (net (code "23") (name "Net-(P3-Pad1)") (class "Default")
      (node (ref "P3") (pin "1") (pinfunction "1_1") (pintype "passive"))
      (node (ref "R55") (pin "2") (pinfunction "2_2") (pintype "passive"))
    )
    (net (code "24") (name "Net-(P3-Pad2)") (class "Default")
      (node (ref "P3") (pin "2") (pinfunction "2_2") (pintype "passive"))
      (node (ref "R39") (pin "2") (pinfunction "2_2") (pintype "passive"))
    )
    (net (code "25") (name "Net-(P3-Pad3)") (class "Default")
      (node (ref "P3") (pin "3") (pinfunction "3_3") (pintype "passive"))
      (node (ref "R23") (pin "2") (pinfunction "2_2") (pintype "passive"))
    )
    (net (code "26") (name "Net-(P3-Pad4)") (class "Default")
      (node (ref "P3") (pin "4") (pinfunction "4_4") (pintype "passive"))
      (node (ref "R7") (pin "2") (pinfunction "2_2") (pintype "passive"))
    )
    (net (code "27") (name "Net-(P3-Pad5)") (class "Default")
      (node (ref "P3") (pin "5") (pinfunction "5_5") (pintype "passive"))
      (node (ref "R56") (pin "2") (pinfunction "2_2") (pintype "passive"))
    )
    (net (code "28") (name "Net-(P3-Pad6)") (class "Default")
      (node (ref "P3") (pin "6") (pinfunction "6_6") (pintype "passive"))
      (node (ref "R40") (pin "2") (pinfunction "2_2") (pintype "passive"))
    )
    (net (code "29") (name "Net-(P3-Pad7)") (class "Default")
      (node (ref "P3") (pin "7") (pinfunction "7_7") (pintype "passive"))
      (node (ref "R24") (pin "2") (pinfunction "2_2") (pintype "passive"))
    )
    (net (code "30") (name "Net-(P3-Pad8)") (class "Default")
      (node (ref "P3") (pin "8") (pinfunction "8_8") (pintype "passive"))
      (node (ref "R8") (pin "2") (pinfunction "2_2") (pintype "passive"))
    )
    (net (code "31") (name "Net-(P4-Pad1)") (class "Default")
      (node (ref "P4") (pin "1") (pinfunction "1_1") (pintype "passive"))
      (node (ref "R57") (pin "2") (pinfunction "2_2") (pintype "passive"))
    )
    (net (code "32") (name "Net-(P4-Pad2)") (class "Default")
      (node (ref "P4") (pin "2") (pinfunction "2_2") (pintype "passive"))
      (node (ref "R41") (pin "2") (pinfunction "2_2") (pintype "passive"))
    )
    (net (code "33") (name "Net-(P4-Pad3)") (class "Default")
      (node (ref "P4") (pin "3") (pinfunction "3_3") (pintype "passive"))
      (node (ref "R25") (pin "2") (pinfunction "2_2") (pintype "passive"))
    )
    (net (code "34") (name "Net-(P4-Pad4)") (class "Default")
      (node (ref "P4") (pin "4") (pinfunction "4_4") (pintype "passive"))
      (node (ref "R9") (pin "2") (pinfunction "2_2") (pintype "passive"))
    )
    (net (code "35") (name "Net-(P4-Pad5)") (class "Default")
      (node (ref "P4") (pin "5") (pinfunction "5_5") (pintype "passive"))
      (node (ref "R58") (pin "2") (pinfunction "2_2") (pintype "passive"))
    )
    (net (code "36") (name "Net-(P4-Pad6)") (class "Default")
      (node (ref "P4") (pin "6") (pinfunction "6_6") (pintype "passive"))
      (node (ref "R42") (pin "2") (pinfunction "2_2") (pintype "passive"))
    )
    (net (code "37") (name "Net-(P4-Pad7)") (class "Default")
      (node (ref "P4") (pin "7") (pinfunction "7_7") (pintype "passive"))
      (node (ref "R26") (pin "2") (pinfunction "2_2") (pintype "passive"))
    )
    (net (code "38") (name "Net-(P4-Pad8)") (class "Default")
      (node (ref "P4") (pin "8") (pinfunction "8_8") (pintype "passive"))
      (node (ref "R10") (pin "2") (pinfunction "2_2") (pintype "passive"))
    )
    (net (code "39") (name "Net-(P5-Pad1)") (class "Default")
      (node (ref "P5") (pin "1") (pinfunction "1_1") (pintype "passive"))
      (node (ref "R59") (pin "2") (pinfunction "2_2") (pintype "passive"))
    )
    (net (code "40") (name "Net-(P5-Pad2)") (class "Default")
      (node (ref "P5") (pin "2") (pinfunction "2_2") (pintype "passive"))
      (node (ref "R43") (pin "2") (pinfunction "2_2") (pintype "passive"))
    )
    (net (code "41") (name "Net-(P5-Pad3)") (class "Default")
      (node (ref "P5") (pin "3") (pinfunction "3_3") (pintype "passive"))
      (node (ref "R27") (pin "2") (pinfunction "2_2") (pintype "passive"))
    )
    (net (code "42") (name "Net-(P5-Pad4)") (class "Default")
      (node (ref "P5") (pin "4") (pinfunction "4_4") (pintype "passive"))
      (node (ref "R11") (pin "2") (pinfunction "2_2") (pintype "passive"))
    )
    (net (code "43") (name "Net-(P5-Pad5)") (class "Default")
      (node (ref "P5") (pin "5") (pinfunction "5_5") (pintype "passive"))
      (node (ref "R60") (pin "2") (pinfunction "2_2") (pintype "passive"))
    )
    (net (code "44") (name "Net-(P5-Pad6)") (class "Default")
      (node (ref "P5") (pin "6") (pinfunction "6_6") (pintype "passive"))
      (node (ref "R44") (pin "2") (pinfunction "2_2") (pintype "passive"))
    )
    (net (code "45") (name "Net-(P5-Pad7)") (class "Default")
      (node (ref "P5") (pin "7") (pinfunction "7_7") (pintype "passive"))
      (node (ref "R28") (pin "2") (pinfunction "2_2") (pintype "passive"))
    )
    (net (code "46") (name "Net-(P5-Pad8)") (class "Default")
      (node (ref "P5") (pin "8") (pinfunction "8_8") (pintype "passive"))
      (node (ref "R12") (pin "2") (pinfunction "2_2") (pintype "passive"))
    )
    (net (code "47") (name "Net-(P6-Pad1)") (class "Default")
      (node (ref "P6") (pin "1") (pinfunction "1_1") (pintype "passive"))
      (node (ref "R61") (pin "2") (pinfunction "2_2") (pintype "passive"))
    )
    (net (code "48") (name "Net-(P6-Pad2)") (class "Default")
      (node (ref "P6") (pin "2") (pinfunction "2_2") (pintype "passive"))
      (node (ref "R45") (pin "2") (pinfunction "2_2") (pintype "passive"))
    )
    (net (code "49") (name "Net-(P6-Pad3)") (class "Default")
      (node (ref "P6") (pin "3") (pinfunction "3_3") (pintype "passive"))
      (node (ref "R29") (pin "2") (pinfunction "2_2") (pintype "passive"))
    )
    (net (code "50") (name "Net-(P6-Pad4)") (class "Default")
      (node (ref "P6") (pin "4") (pinfunction "4_4") (pintype "passive"))
      (node (ref "R13") (pin "2") (pinfunction "2_2") (pintype "passive"))
    )
    (net (code "51") (name "Net-(P6-Pad5)") (class "Default")
      (node (ref "P6") (pin "5") (pinfunction "5_5") (pintype "passive"))
      (node (ref "R62") (pin "2") (pinfunction "2_2") (pintype "passive"))
    )
    (net (code "52") (name "Net-(P6-Pad6)") (class "Default")
      (node (ref "P6") (pin "6") (pinfunction "6_6") (pintype "passive"))
      (node (ref "R46") (pin "2") (pinfunction "2_2") (pintype "passive"))
    )
    (net (code "53") (name "Net-(P6-Pad7)") (class "Default")
      (node (ref "P6") (pin "7") (pinfunction "7_7") (pintype "passive"))
      (node (ref "R30") (pin "2") (pinfunction "2_2") (pintype "passive"))
    )
    (net (code "54") (name "Net-(P6-Pad8)") (class "Default")
      (node (ref "P6") (pin "8") (pinfunction "8_8") (pintype "passive"))
      (node (ref "R14") (pin "2") (pinfunction "2_2") (pintype "passive"))
    )
    (net (code "55") (name "Net-(P7-Pad1)") (class "Default")
      (node (ref "P7") (pin "1") (pinfunction "1_1") (pintype "passive"))
      (node (ref "R63") (pin "2") (pinfunction "2_2") (pintype "passive"))
    )
    (net (code "56") (name "Net-(P7-Pad2)") (class "Default")
      (node (ref "P7") (pin "2") (pinfunction "2_2") (pintype "passive"))
      (node (ref "R47") (pin "2") (pinfunction "2_2") (pintype "passive"))
    )
    (net (code "57") (name "Net-(P7-Pad3)") (class "Default")
      (node (ref "P7") (pin "3") (pinfunction "3_3") (pintype "passive"))
      (node (ref "R31") (pin "2") (pinfunction "2_2") (pintype "passive"))
    )
    (net (code "58") (name "Net-(P7-Pad4)") (class "Default")
      (node (ref "P7") (pin "4") (pinfunction "4_4") (pintype "passive"))
      (node (ref "R15") (pin "2") (pinfunction "2_2") (pintype "passive"))
    )
    (net (code "59") (name "Net-(P7-Pad5)") (class "Default")
      (node (ref "P7") (pin "5") (pinfunction "5_5") (pintype "passive"))
      (node (ref "R64") (pin "2") (pinfunction "2_2") (pintype "passive"))
    )
    (net (code "60") (name "Net-(P7-Pad6)") (class "Default")
      (node (ref "P7") (pin "6") (pinfunction "6_6") (pintype "passive"))
      (node (ref "R48") (pin "2") (pinfunction "2_2") (pintype "passive"))
    )
    (net (code "61") (name "Net-(P7-Pad7)") (class "Default")
      (node (ref "P7") (pin "7") (pinfunction "7_7") (pintype "passive"))
      (node (ref "R32") (pin "2") (pinfunction "2_2") (pintype "passive"))
    )
    (net (code "62") (name "Net-(P7-Pad8)") (class "Default")
      (node (ref "P7") (pin "8") (pinfunction "8_8") (pintype "passive"))
      (node (ref "R16") (pin "2") (pinfunction "2_2") (pintype "passive"))
    )
    (net (code "63") (name "Net-(P8-Pad1)") (class "Default")
      (node (ref "P8") (pin "1") (pinfunction "1_1") (pintype "passive"))
      (node (ref "R65") (pin "2") (pinfunction "2_2") (pintype "passive"))
    )
    (net (code "64") (name "Net-(P8-Pad2)") (class "Default")
      (node (ref "P8") (pin "2") (pinfunction "2_2") (pintype "passive"))
      (node (ref "R49") (pin "2") (pinfunction "2_2") (pintype "passive"))
    )
    (net (code "65") (name "Net-(P8-Pad3)") (class "Default")
      (node (ref "P8") (pin "3") (pinfunction "3_3") (pintype "passive"))
      (node (ref "R33") (pin "2") (pinfunction "2_2") (pintype "passive"))
    )
    (net (code "66") (name "Net-(P8-Pad4)") (class "Default")
      (node (ref "P8") (pin "4") (pinfunction "4_4") (pintype "passive"))
      (node (ref "R17") (pin "2") (pinfunction "2_2") (pintype "passive"))
    )
    (net (code "67") (name "Net-(P8-Pad5)") (class "Default")
      (node (ref "P8") (pin "5") (pinfunction "5_5") (pintype "passive"))
      (node (ref "R66") (pin "2") (pinfunction "2_2") (pintype "passive"))
    )
    (net (code "68") (name "Net-(P8-Pad6)") (class "Default")
      (node (ref "P8") (pin "6") (pinfunction "6_6") (pintype "passive"))
      (node (ref "R50") (pin "2") (pinfunction "2_2") (pintype "passive"))
    )
    (net (code "69") (name "Net-(P8-Pad7)") (class "Default")
      (node (ref "P8") (pin "7") (pinfunction "7_7") (pintype "passive"))
      (node (ref "R34") (pin "2") (pinfunction "2_2") (pintype "passive"))
    )
    (net (code "70") (name "Net-(P8-Pad8)") (class "Default")
      (node (ref "P8") (pin "8") (pinfunction "8_8") (pintype "passive"))
      (node (ref "R18") (pin "2") (pinfunction "2_2") (pintype "passive"))
    )
    (net (code "71") (name "Net-(Q1-B)") (class "Default")
      (node (ref "Q1") (pin "1") (pinfunction "B_1") (pintype "passive"))
      (node (ref "R69") (pin "2") (pinfunction "2_2") (pintype "passive"))
    )
    (net (code "72") (name "Net-(Q1-C)") (class "Default")
      (node (ref "P9") (pin "8") (pinfunction "8_8") (pintype "passive"))
      (node (ref "Q1") (pin "2") (pinfunction "C_2") (pintype "passive"))
    )
    (net (code "73") (name "Net-(Q2-B)") (class "Default")
      (node (ref "Q2") (pin "1") (pinfunction "B_1") (pintype "passive"))
      (node (ref "R71") (pin "2") (pinfunction "2_2") (pintype "passive"))
    )
    (net (code "74") (name "Net-(Q2-C)") (class "Default")
      (node (ref "P9") (pin "7") (pinfunction "7_7") (pintype "passive"))
      (node (ref "Q2") (pin "2") (pinfunction "C_2") (pintype "passive"))
    )
    (net (code "75") (name "Net-(Q3-B)") (class "Default")
      (node (ref "Q3") (pin "1") (pinfunction "B_1") (pintype "passive"))
      (node (ref "R73") (pin "2") (pinfunction "2_2") (pintype "passive"))
    )
    (net (code "76") (name "Net-(Q3-C)") (class "Default")
      (node (ref "P9") (pin "6") (pinfunction "6_6") (pintype "passive"))
      (node (ref "Q3") (pin "2") (pinfunction "C_2") (pintype "passive"))
    )
    (net (code "77") (name "Net-(Q4-B)") (class "Default")
      (node (ref "Q4") (pin "1") (pinfunction "B_1") (pintype "passive"))
      (node (ref "R75") (pin "2") (pinfunction "2_2") (pintype "passive"))
    )
    (net (code "78") (name "Net-(Q4-C)") (class "Default")
      (node (ref "P9") (pin "5") (pinfunction "5_5") (pintype "passive"))
      (node (ref "Q4") (pin "2") (pinfunction "C_2") (pintype "passive"))
    )
    (net (code "79") (name "Net-(Q5-B)") (class "Default")
      (node (ref "Q5") (pin "1") (pinfunction "B_1") (pintype "passive"))
      (node (ref "R68") (pin "2") (pinfunction "2_2") (pintype "passive"))
    )
    (net (code "80") (name "Net-(Q5-C)") (class "Default")
      (node (ref "P9") (pin "4") (pinfunction "4_4") (pintype "passive"))
      (node (ref "Q5") (pin "2") (pinfunction "C_2") (pintype "passive"))
    )
    (net (code "81") (name "Net-(Q6-B)") (class "Default")
      (node (ref "Q6") (pin "1") (pinfunction "B_1") (pintype "passive"))
      (node (ref "R70") (pin "2") (pinfunction "2_2") (pintype "passive"))
    )
    (net (code "82") (name "Net-(Q6-C)") (class "Default")
      (node (ref "P9") (pin "3") (pinfunction "3_3") (pintype "passive"))
      (node (ref "Q6") (pin "2") (pinfunction "C_2") (pintype "passive"))
    )
    (net (code "83") (name "Net-(Q7-B)") (class "Default")
      (node (ref "Q7") (pin "1") (pinfunction "B_1") (pintype "passive"))
      (node (ref "R72") (pin "2") (pinfunction "2_2") (pintype "passive"))
    )
    (net (code "84") (name "Net-(Q7-C)") (class "Default")
      (node (ref "P9") (pin "2") (pinfunction "2_2") (pintype "passive"))
      (node (ref "Q7") (pin "2") (pinfunction "C_2") (pintype "passive"))
    )
    (net (code "85") (name "Net-(Q8-B)") (class "Default")
      (node (ref "Q8") (pin "1") (pinfunction "B_1") (pintype "passive"))
      (node (ref "R74") (pin "2") (pinfunction "2_2") (pintype "passive"))
    )
    (net (code "86") (name "Net-(Q8-C)") (class "Default")
      (node (ref "P9") (pin "1") (pinfunction "1_1") (pintype "passive"))
      (node (ref "Q8") (pin "2") (pinfunction "C_2") (pintype "passive"))
    )
    (net (code "87") (name "Net-(R67-Pad1)") (class "Default")
      (node (ref "R67") (pin "1") (pinfunction "1_1") (pintype "passive"))
      (node (ref "SW1") (pin "2") (pinfunction "2_2") (pintype "passive"))
    )
    (net (code "88") (name "Net-(U1-3V3)") (class "Default")
      (node (ref "R67") (pin "2") (pinfunction "2_2") (pintype "passive"))
      (node (ref "U1") (pin "J2_1") (pinfunction "3V3_J2_1") (pintype "power_in"))
    )
    (net (code "89") (name "Net-(U1-IO23)") (class "Default")
      (node (ref "U1") (pin "J3_2") (pinfunction "IO23_J3_2") (pintype "bidirectional"))
      (node (ref "U2") (pin "14") (pinfunction "A_14") (pintype "input"))
    )
    (net (code "90") (name "Net-(U1-IO32)") (class "Default")
      (node (ref "SW1") (pin "1") (pinfunction "1_1") (pintype "passive"))
      (node (ref "U1") (pin "J2_7") (pinfunction "IO32_J2_7") (pintype "bidirectional"))
    )
    (net (code "91") (name "Net-(U2-QA)") (class "Default")
      (node (ref "R51") (pin "1") (pinfunction "1_1") (pintype "passive"))
      (node (ref "U2") (pin "15") (pinfunction "QA_15") (pintype "input"))
    )
    (net (code "92") (name "Net-(U2-QB)") (class "Default")
      (node (ref "R35") (pin "1") (pinfunction "1_1") (pintype "passive"))
      (node (ref "U2") (pin "1") (pinfunction "QB_1") (pintype "output"))
    )
    (net (code "93") (name "Net-(U2-QC)") (class "Default")
      (node (ref "R19") (pin "1") (pinfunction "1_1") (pintype "passive"))
      (node (ref "U2") (pin "2") (pinfunction "QC_2") (pintype "output"))
    )
    (net (code "94") (name "Net-(U2-QD)") (class "Default")
      (node (ref "R3") (pin "1") (pinfunction "1_1") (pintype "passive"))
      (node (ref "U2") (pin "3") (pinfunction "QD_3") (pintype "output"))
    )
    (net (code "95") (name "Net-(U2-QE)") (class "Default")
      (node (ref "R52") (pin "1") (pinfunction "1_1") (pintype "passive"))
      (node (ref "U2") (pin "4") (pinfunction "QE_4") (pintype "output"))
    )
    (net (code "96") (name "Net-(U2-QF)") (class "Default")
      (node (ref "R36") (pin "1") (pinfunction "1_1") (pintype "passive"))
      (node (ref "U2") (pin "5") (pinfunction "QF_5") (pintype "output"))
    )
    (net (code "97") (name "Net-(U2-QG)") (class "Default")
      (node (ref "R20") (pin "1") (pinfunction "1_1") (pintype "passive"))
      (node (ref "U2") (pin "6") (pinfunction "QG_6") (pintype "output"))
    )
    (net (code "98") (name "Net-(U2-QH)") (class "Default")
      (node (ref "R4") (pin "1") (pinfunction "1_1") (pintype "passive"))
      (node (ref "U2") (pin "7") (pinfunction "QH_7") (pintype "output"))
    )
    (net (code "99") (name "Net-(U2-SQH)") (class "Default")
      (node (ref "U2") (pin "9") (pinfunction "SQH_9") (pintype "output"))
      (node (ref "U3") (pin "14") (pinfunction "A_14") (pintype "input"))
    )
    (net (code "100") (name "Net-(U3-QA)") (class "Default")
      (node (ref "R53") (pin "1") (pinfunction "1_1") (pintype "passive"))
      (node (ref "U3") (pin "15") (pinfunction "QA_15") (pintype "input"))
    )
    (net (code "101") (name "Net-(U3-QB)") (class "Default")
      (node (ref "R37") (pin "1") (pinfunction "1_1") (pintype "passive"))
      (node (ref "U3") (pin "1") (pinfunction "QB_1") (pintype "output"))
    )
    (net (code "102") (name "Net-(U3-QC)") (class "Default")
      (node (ref "R21") (pin "1") (pinfunction "1_1") (pintype "passive"))
      (node (ref "U3") (pin "2") (pinfunction "QC_2") (pintype "output"))
    )
    (net (code "103") (name "Net-(U3-QD)") (class "Default")
      (node (ref "R5") (pin "1") (pinfunction "1_1") (pintype "passive"))
      (node (ref "U3") (pin "3") (pinfunction "QD_3") (pintype "output"))
    )
    (net (code "104") (name "Net-(U3-QE)") (class "Default")
      (node (ref "R54") (pin "1") (pinfunction "1_1") (pintype "passive"))
      (node (ref "U3") (pin "4") (pinfunction "QE_4") (pintype "output"))
    )
    (net (code "105") (name "Net-(U3-QF)") (class "Default")
      (node (ref "R38") (pin "1") (pinfunction "1_1") (pintype "passive"))
      (node (ref "U3") (pin "5") (pinfunction "QF_5") (pintype "output"))
    )
    (net (code "106") (name "Net-(U3-QG)") (class "Default")
      (node (ref "R22") (pin "1") (pinfunction "1_1") (pintype "passive"))
      (node (ref "U3") (pin "6") (pinfunction "QG_6") (pintype "output"))
    )
    (net (code "107") (name "Net-(U3-QH)") (class "Default")
      (node (ref "R6") (pin "1") (pinfunction "1_1") (pintype "passive"))
      (node (ref "U3") (pin "7") (pinfunction "QH_7") (pintype "output"))
    )
    (net (code "108") (name "Net-(U3-SQH)") (class "Default")
      (node (ref "U3") (pin "9") (pinfunction "SQH_9") (pintype "output"))
      (node (ref "U4") (pin "14") (pinfunction "A_14") (pintype "input"))
    )
    (net (code "109") (name "Net-(U4-QA)") (class "Default")
      (node (ref "R55") (pin "1") (pinfunction "1_1") (pintype "passive"))
      (node (ref "U4") (pin "15") (pinfunction "QA_15") (pintype "input"))
    )
    (net (code "110") (name "Net-(U4-QB)") (class "Default")
      (node (ref "R39") (pin "1") (pinfunction "1_1") (pintype "passive"))
      (node (ref "U4") (pin "1") (pinfunction "QB_1") (pintype "output"))
    )
    (net (code "111") (name "Net-(U4-QC)") (class "Default")
      (node (ref "R23") (pin "1") (pinfunction "1_1") (pintype "passive"))
      (node (ref "U4") (pin "2") (pinfunction "QC_2") (pintype "output"))
    )
    (net (code "112") (name "Net-(U4-QD)") (class "Default")
      (node (ref "R7") (pin "1") (pinfunction "1_1") (pintype "passive"))
      (node (ref "U4") (pin "3") (pinfunction "QD_3") (pintype "output"))
    )
    (net (code "113") (name "Net-(U4-QE)") (class "Default")
      (node (ref "R56") (pin "1") (pinfunction "1_1") (pintype "passive"))
      (node (ref "U4") (pin "4") (pinfunction "QE_4") (pintype "output"))
    )
    (net (code "114") (name "Net-(U4-QF)") (class "Default")
      (node (ref "R40") (pin "1") (pinfunction "1_1") (pintype "passive"))
      (node (ref "U4") (pin "5") (pinfunction "QF_5") (pintype "output"))
    )
    (net (code "115") (name "Net-(U4-QG)") (class "Default")
      (node (ref "R24") (pin "1") (pinfunction "1_1") (pintype "passive"))
      (node (ref "U4") (pin "6") (pinfunction "QG_6") (pintype "output"))
    )
    (net (code "116") (name "Net-(U4-QH)") (class "Default")
      (node (ref "R8") (pin "1") (pinfunction "1_1") (pintype "passive"))
      (node (ref "U4") (pin "7") (pinfunction "QH_7") (pintype "output"))
    )
    (net (code "117") (name "Net-(U4-SQH)") (class "Default")
      (node (ref "U4") (pin "9") (pinfunction "SQH_9") (pintype "output"))
      (node (ref "U5") (pin "14") (pinfunction "A_14") (pintype "input"))
    )
    (net (code "118") (name "Net-(U5-QA)") (class "Default")
      (node (ref "R57") (pin "1") (pinfunction "1_1") (pintype "passive"))
      (node (ref "U5") (pin "15") (pinfunction "QA_15") (pintype "input"))
    )
    (net (code "119") (name "Net-(U5-QB)") (class "Default")
      (node (ref "R41") (pin "1") (pinfunction "1_1") (pintype "passive"))
      (node (ref "U5") (pin "1") (pinfunction "QB_1") (pintype "output"))
    )
    (net (code "120") (name "Net-(U5-QC)") (class "Default")
      (node (ref "R25") (pin "1") (pinfunction "1_1") (pintype "passive"))
      (node (ref "U5") (pin "2") (pinfunction "QC_2") (pintype "output"))
    )
    (net (code "121") (name "Net-(U5-QD)") (class "Default")
      (node (ref "R9") (pin "1") (pinfunction "1_1") (pintype "passive"))
      (node (ref "U5") (pin "3") (pinfunction "QD_3") (pintype "output"))
    )
    (net (code "122") (name "Net-(U5-QE)") (class "Default")
      (node (ref "R58") (pin "1") (pinfunction "1_1") (pintype "passive"))
      (node (ref "U5") (pin "4") (pinfunction "QE_4") (pintype "output"))
    )
    (net (code "123") (name "Net-(U5-QF)") (class "Default")
      (node (ref "R42") (pin "1") (pinfunction "1_1") (pintype "passive"))
      (node (ref "U5") (pin "5") (pinfunction "QF_5") (pintype "output"))
    )
    (net (code "124") (name "Net-(U5-QG)") (class "Default")
      (node (ref "R26") (pin "1") (pinfunction "1_1") (pintype "passive"))
      (node (ref "U5") (pin "6") (pinfunction "QG_6") (pintype "output"))
    )
    (net (code "125") (name "Net-(U5-QH)") (class "Default")
      (node (ref "R10") (pin "1") (pinfunction "1_1") (pintype "passive"))
      (node (ref "U5") (pin "7") (pinfunction "QH_7") (pintype "output"))
    )
    (net (code "126") (name "Net-(U5-SQH)") (class "Default")
      (node (ref "U5") (pin "9") (pinfunction "SQH_9") (pintype "output"))
      (node (ref "U6") (pin "14") (pinfunction "A_14") (pintype "input"))
    )
    (net (code "127") (name "Net-(U6-QA)") (class "Default")
      (node (ref "R59") (pin "1") (pinfunction "1_1") (pintype "passive"))
      (node (ref "U6") (pin "15") (pinfunction "QA_15") (pintype "input"))
    )
    (net (code "128") (name "Net-(U6-QB)") (class "Default")
      (node (ref "R43") (pin "1") (pinfunction "1_1") (pintype "passive"))
      (node (ref "U6") (pin "1") (pinfunction "QB_1") (pintype "output"))
    )
    (net (code "129") (name "Net-(U6-QC)") (class "Default")
      (node (ref "R27") (pin "1") (pinfunction "1_1") (pintype "passive"))
      (node (ref "U6") (pin "2") (pinfunction "QC_2") (pintype "output"))
    )
    (net (code "130") (name "Net-(U6-QD)") (class "Default")
      (node (ref "R11") (pin "1") (pinfunction "1_1") (pintype "passive"))
      (node (ref "U6") (pin "3") (pinfunction "QD_3") (pintype "output"))
    )
    (net (code "131") (name "Net-(U6-QE)") (class "Default")
      (node (ref "R60") (pin "1") (pinfunction "1_1") (pintype "passive"))
      (node (ref "U6") (pin "4") (pinfunction "QE_4") (pintype "output"))
    )
    (net (code "132") (name "Net-(U6-QF)") (class "Default")
      (node (ref "R44") (pin "1") (pinfunction "1_1") (pintype "passive"))
      (node (ref "U6") (pin "5") (pinfunction "QF_5") (pintype "output"))
    )
    (net (code "133") (name "Net-(U6-QG)") (class "Default")
      (node (ref "R28") (pin "1") (pinfunction "1_1") (pintype "passive"))
      (node (ref "U6") (pin "6") (pinfunction "QG_6") (pintype "output"))
    )
    (net (code "134") (name "Net-(U6-QH)") (class "Default")
      (node (ref "R12") (pin "1") (pinfunction "1_1") (pintype "passive"))
      (node (ref "U6") (pin "7") (pinfunction "QH_7") (pintype "output"))
    )
    (net (code "135") (name "Net-(U6-SQH)") (class "Default")
      (node (ref "U6") (pin "9") (pinfunction "SQH_9") (pintype "output"))
      (node (ref "U7") (pin "14") (pinfunction "A_14") (pintype "input"))
    )
    (net (code "136") (name "Net-(U7-QA)") (class "Default")
      (node (ref "R61") (pin "1") (pinfunction "1_1") (pintype "passive"))
      (node (ref "U7") (pin "15") (pinfunction "QA_15") (pintype "input"))
    )
    (net (code "137") (name "Net-(U7-QB)") (class "Default")
      (node (ref "R45") (pin "1") (pinfunction "1_1") (pintype "passive"))
      (node (ref "U7") (pin "1") (pinfunction "QB_1") (pintype "output"))
    )
    (net (code "138") (name "Net-(U7-QC)") (class "Default")
      (node (ref "R29") (pin "1") (pinfunction "1_1") (pintype "passive"))
      (node (ref "U7") (pin "2") (pinfunction "QC_2") (pintype "output"))
    )
    (net (code "139") (name "Net-(U7-QD)") (class "Default")
      (node (ref "R13") (pin "1") (pinfunction "1_1") (pintype "passive"))
      (node (ref "U7") (pin "3") (pinfunction "QD_3") (pintype "output"))
    )
    (net (code "140") (name "Net-(U7-QE)") (class "Default")
      (node (ref "R62") (pin "1") (pinfunction "1_1") (pintype "passive"))
      (node (ref "U7") (pin "4") (pinfunction "QE_4") (pintype "output"))
    )
    (net (code "141") (name "Net-(U7-QF)") (class "Default")
      (node (ref "R46") (pin "1") (pinfunction "1_1") (pintype "passive"))
      (node (ref "U7") (pin "5") (pinfunction "QF_5") (pintype "output"))
    )
    (net (code "142") (name "Net-(U7-QG)") (class "Default")
      (node (ref "R30") (pin "1") (pinfunction "1_1") (pintype "passive"))
      (node (ref "U7") (pin "6") (pinfunction "QG_6") (pintype "output"))
    )
    (net (code "143") (name "Net-(U7-QH)") (class "Default")
      (node (ref "R14") (pin "1") (pinfunction "1_1") (pintype "passive"))
      (node (ref "U7") (pin "7") (pinfunction "QH_7") (pintype "output"))
    )
    (net (code "144") (name "Net-(U7-SQH)") (class "Default")
      (node (ref "U7") (pin "9") (pinfunction "SQH_9") (pintype "output"))
      (node (ref "U8") (pin "14") (pinfunction "A_14") (pintype "input"))
    )
    (net (code "145") (name "Net-(U8-QA)") (class "Default")
      (node (ref "R63") (pin "1") (pinfunction "1_1") (pintype "passive"))
      (node (ref "U8") (pin "15") (pinfunction "QA_15") (pintype "input"))
    )
    (net (code "146") (name "Net-(U8-QB)") (class "Default")
      (node (ref "R47") (pin "1") (pinfunction "1_1") (pintype "passive"))
      (node (ref "U8") (pin "1") (pinfunction "QB_1") (pintype "output"))
    )
    (net (code "147") (name "Net-(U8-QC)") (class "Default")
      (node (ref "R31") (pin "1") (pinfunction "1_1") (pintype "passive"))
      (node (ref "U8") (pin "2") (pinfunction "QC_2") (pintype "output"))
    )
    (net (code "148") (name "Net-(U8-QD)") (class "Default")
      (node (ref "R15") (pin "1") (pinfunction "1_1") (pintype "passive"))
      (node (ref "U8") (pin "3") (pinfunction "QD_3") (pintype "output"))
    )
    (net (code "149") (name "Net-(U8-QE)") (class "Default")
      (node (ref "R64") (pin "1") (pinfunction "1_1") (pintype "passive"))
      (node (ref "U8") (pin "4") (pinfunction "QE_4") (pintype "output"))
    )
    (net (code "150") (name "Net-(U8-QF)") (class "Default")
      (node (ref "R48") (pin "1") (pinfunction "1_1") (pintype "passive"))
      (node (ref "U8") (pin "5") (pinfunction "QF_5") (pintype "output"))
    )
    (net (code "151") (name "Net-(U8-QG)") (class "Default")
      (node (ref "R32") (pin "1") (pinfunction "1_1") (pintype "passive"))
      (node (ref "U8") (pin "6") (pinfunction "QG_6") (pintype "output"))
    )
    (net (code "152") (name "Net-(U8-QH)") (class "Default")
      (node (ref "R16") (pin "1") (pinfunction "1_1") (pintype "passive"))
      (node (ref "U8") (pin "7") (pinfunction "QH_7") (pintype "output"))
    )
    (net (code "153") (name "Net-(U8-SQH)") (class "Default")
      (node (ref "U8") (pin "9") (pinfunction "SQH_9") (pintype "output"))
      (node (ref "U9") (pin "14") (pinfunction "A_14") (pintype "input"))
    )
    (net (code "154") (name "Net-(U9-QA)") (class "Default")
      (node (ref "R65") (pin "1") (pinfunction "1_1") (pintype "passive"))
      (node (ref "U9") (pin "15") (pinfunction "QA_15") (pintype "input"))
    )
    (net (code "155") (name "Net-(U9-QB)") (class "Default")
      (node (ref "R49") (pin "1") (pinfunction "1_1") (pintype "passive"))
      (node (ref "U9") (pin "1") (pinfunction "QB_1") (pintype "output"))
    )
    (net (code "156") (name "Net-(U9-QC)") (class "Default")
      (node (ref "R33") (pin "1") (pinfunction "1_1") (pintype "passive"))
      (node (ref "U9") (pin "2") (pinfunction "QC_2") (pintype "output"))
    )
    (net (code "157") (name "Net-(U9-QD)") (class "Default")
      (node (ref "R17") (pin "1") (pinfunction "1_1") (pintype "passive"))
      (node (ref "U9") (pin "3") (pinfunction "QD_3") (pintype "output"))
    )
    (net (code "158") (name "Net-(U9-QE)") (class "Default")
      (node (ref "R66") (pin "1") (pinfunction "1_1") (pintype "passive"))
      (node (ref "U9") (pin "4") (pinfunction "QE_4") (pintype "output"))
    )
    (net (code "159") (name "Net-(U9-QF)") (class "Default")
      (node (ref "R50") (pin "1") (pinfunction "1_1") (pintype "passive"))
      (node (ref "U9") (pin "5") (pinfunction "QF_5") (pintype "output"))
    )
    (net (code "160") (name "Net-(U9-QG)") (class "Default")
      (node (ref "R34") (pin "1") (pinfunction "1_1") (pintype "passive"))
      (node (ref "U9") (pin "6") (pinfunction "QG_6") (pintype "output"))
    )
    (net (code "161") (name "Net-(U9-QH)") (class "Default")
      (node (ref "R18") (pin "1") (pinfunction "1_1") (pintype "passive"))
      (node (ref "U9") (pin "7") (pinfunction "QH_7") (pintype "output"))
    )
    (net (code "162") (name "Net-(U10-A)") (class "Default")
      (node (ref "U10") (pin "14") (pinfunction "A_14") (pintype "input"))
      (node (ref "U9") (pin "9") (pinfunction "SQH_9") (pintype "output"))
    )
    (net (code "163") (name "Net-(U10-QA)") (class "Default")
      (node (ref "R74") (pin "1") (pinfunction "1_1") (pintype "passive"))
      (node (ref "U10") (pin "15") (pinfunction "QA_15") (pintype "input"))
    )
    (net (code "164") (name "Net-(U10-QB)") (class "Default")
      (node (ref "R72") (pin "1") (pinfunction "1_1") (pintype "passive"))
      (node (ref "U10") (pin "1") (pinfunction "QB_1") (pintype "output"))
    )
    (net (code "165") (name "Net-(U10-QC)") (class "Default")
      (node (ref "R70") (pin "1") (pinfunction "1_1") (pintype "passive"))
      (node (ref "U10") (pin "2") (pinfunction "QC_2") (pintype "output"))
    )
    (net (code "166") (name "Net-(U10-QD)") (class "Default")
      (node (ref "R68") (pin "1") (pinfunction "1_1") (pintype "passive"))
      (node (ref "U10") (pin "3") (pinfunction "QD_3") (pintype "output"))
    )
    (net (code "167") (name "Net-(U10-QE)") (class "Default")
      (node (ref "R75") (pin "1") (pinfunction "1_1") (pintype "passive"))
      (node (ref "U10") (pin "4") (pinfunction "QE_4") (pintype "output"))
    )
    (net (code "168") (name "Net-(U10-QF)") (class "Default")
      (node (ref "R73") (pin "1") (pinfunction "1_1") (pintype "passive"))
      (node (ref "U10") (pin "5") (pinfunction "QF_5") (pintype "output"))
    )
    (net (code "169") (name "Net-(U10-QG)") (class "Default")
      (node (ref "R71") (pin "1") (pinfunction "1_1") (pintype "passive"))
      (node (ref "U10") (pin "6") (pinfunction "QG_6") (pintype "output"))
    )
    (net (code "170") (name "Net-(U10-QH)") (class "Default")
      (node (ref "R69") (pin "1") (pinfunction "1_1") (pintype "passive"))
      (node (ref "U10") (pin "7") (pinfunction "QH_7") (pintype "output"))
    )
    (net (code "171") (name "unconnected-(J1-CC2-PadB5)") (class "Default")
      (node (ref "J1") (pin "B5") (pinfunction "CC2_B5") (pintype "bidirectional"))
    )
    (net (code "172") (name "unconnected-(J1-Dn1-PadA7)") (class "Default")
      (node (ref "J1") (pin "A7") (pinfunction "Dn1_A7") (pintype "bidirectional"))
    )
    (net (code "173") (name "unconnected-(J1-Dn2-PadB7)") (class "Default")
      (node (ref "J1") (pin "B7") (pinfunction "Dn2_B7") (pintype "bidirectional"))
    )
    (net (code "174") (name "unconnected-(J1-Dp1-PadA6)") (class "Default")
      (node (ref "J1") (pin "A6") (pinfunction "Dp1_A6") (pintype "bidirectional"))
    )
    (net (code "175") (name "unconnected-(J1-Dp2-PadB6)") (class "Default")
      (node (ref "J1") (pin "B6") (pinfunction "Dp2_B6") (pintype "bidirectional"))
    )
    (net (code "176") (name "unconnected-(J1-SBU1-PadA8)") (class "Default")
      (node (ref "J1") (pin "A8") (pinfunction "SBU1_A8") (pintype "bidirectional"))
    )
    (net (code "177") (name "unconnected-(SW1-Pad3)") (class "Default")
      (node (ref "SW1") (pin "3") (pinfunction "3_3") (pintype "passive"))
    )
    (net (code "178") (name "unconnected-(U1-CLK-PadJ3_19)") (class "Default")
      (node (ref "U1") (pin "J3_19") (pinfunction "CLK_J3_19") (pintype "bidirectional"))
    )
    (net (code "179") (name "unconnected-(U1-CMD-PadJ2_18)") (class "Default")
      (node (ref "U1") (pin "J2_18") (pinfunction "CMD_J2_18") (pintype "bidirectional"))
    )
    (net (code "180") (name "unconnected-(U1-EN-PadJ2_2)") (class "Default")
      (node (ref "U1") (pin "J2_2") (pinfunction "EN_J2_2") (pintype "input+no_connect"))
    )
    (net (code "181") (name "unconnected-(U1-IO0-PadJ3_14)") (class "Default")
      (node (ref "U1") (pin "J3_14") (pinfunction "IO0_J3_14") (pintype "bidirectional"))
    )
    (net (code "182") (name "unconnected-(U1-IO2-PadJ3_15)") (class "Default")
      (node (ref "U1") (pin "J3_15") (pinfunction "IO2_J3_15") (pintype "bidirectional"))
    )
    (net (code "183") (name "unconnected-(U1-IO4-PadJ3_13)") (class "Default")
      (node (ref "U1") (pin "J3_13") (pinfunction "IO4_J3_13") (pintype "bidirectional"))
    )
    (net (code "184") (name "unconnected-(U1-IO5-PadJ3_10)") (class "Default")
      (node (ref "U1") (pin "J3_10") (pinfunction "IO5_J3_10") (pintype "bidirectional"))
    )
    (net (code "185") (name "unconnected-(U1-IO12-PadJ2_13)") (class "Default")
      (node (ref "U1") (pin "J2_13") (pinfunction "IO12_J2_13") (pintype "bidirectional"))
    )
    (net (code "186") (name "unconnected-(U1-IO13-PadJ2_15)") (class "Default")
      (node (ref "U1") (pin "J2_15") (pinfunction "IO13_J2_15") (pintype "bidirectional"))
    )
    (net (code "187") (name "unconnected-(U1-IO14-PadJ2_12)") (class "Default")
      (node (ref "U1") (pin "J2_12") (pinfunction "IO14_J2_12") (pintype "bidirectional"))
    )
    (net (code "188") (name "unconnected-(U1-IO15-PadJ3_16)") (class "Default")
      (node (ref "U1") (pin "J3_16") (pinfunction "IO15_J3_16") (pintype "bidirectional"))
    )
    (net (code "189") (name "unconnected-(U1-IO16-PadJ3_12)") (class "Default")
      (node (ref "U1") (pin "J3_12") (pinfunction "IO16_J3_12") (pintype "bidirectional"))
    )
    (net (code "190") (name "unconnected-(U1-IO17-PadJ3_11)") (class "Default")
      (node (ref "U1") (pin "J3_11") (pinfunction "IO17_J3_11") (pintype "bidirectional"))
    )
    (net (code "191") (name "unconnected-(U1-IO18-PadJ3_9)") (class "Default")
      (node (ref "U1") (pin "J3_9") (pinfunction "IO18_J3_9") (pintype "bidirectional"))
    )
    (net (code "192") (name "unconnected-(U1-IO22-PadJ3_3)") (class "Default")
      (node (ref "U1") (pin "J3_3") (pinfunction "IO22_J3_3") (pintype "bidirectional"))
    )
    (net (code "193") (name "unconnected-(U1-IO25-PadJ2_9)") (class "Default")
      (node (ref "U1") (pin "J2_9") (pinfunction "IO25_J2_9") (pintype "bidirectional"))
    )
    (net (code "194") (name "unconnected-(U1-IO26-PadJ2_10)") (class "Default")
      (node (ref "U1") (pin "J2_10") (pinfunction "IO26_J2_10") (pintype "bidirectional"))
    )
    (net (code "195") (name "unconnected-(U1-IO27-PadJ2_11)") (class "Default")
      (node (ref "U1") (pin "J2_11") (pinfunction "IO27_J2_11") (pintype "bidirectional"))
    )
    (net (code "196") (name "unconnected-(U1-IO33-PadJ2_8)") (class "Default")
      (node (ref "U1") (pin "J2_8") (pinfunction "IO33_J2_8") (pintype "bidirectional"))
    )
    (net (code "197") (name "unconnected-(U1-IO34-PadJ2_5)") (class "Default")
      (node (ref "U1") (pin "J2_5") (pinfunction "IO34_J2_5") (pintype "bidirectional"))
    )
    (net (code "198") (name "unconnected-(U1-IO35-PadJ2_6)") (class "Default")
      (node (ref "U1") (pin "J2_6") (pinfunction "IO35_J2_6") (pintype "bidirectional"))
    )
    (net (code "199") (name "unconnected-(U1-RXD0-PadJ3_5)") (class "Default")
      (node (ref "U1") (pin "J3_5") (pinfunction "RXD0_J3_5") (pintype "bidirectional"))
    )
    (net (code "200") (name "unconnected-(U1-SD0-PadJ3_18)") (class "Default")
      (node (ref "U1") (pin "J3_18") (pinfunction "SD0_J3_18") (pintype "bidirectional"))
    )
    (net (code "201") (name "unconnected-(U1-SD1-PadJ3_17)") (class "Default")
      (node (ref "U1") (pin "J3_17") (pinfunction "SD1_J3_17") (pintype "bidirectional"))
    )
    (net (code "202") (name "unconnected-(U1-SD2-PadJ2_16)") (class "Default")
      (node (ref "U1") (pin "J2_16") (pinfunction "SD2_J2_16") (pintype "bidirectional"))
    )
    (net (code "203") (name "unconnected-(U1-SD3-PadJ2_17)") (class "Default")
      (node (ref "U1") (pin "J2_17") (pinfunction "SD3_J2_17") (pintype "bidirectional"))
    )
    (net (code "204") (name "unconnected-(U1-SENSOR_VN-PadJ2_4)") (class "Default")
      (node (ref "U1") (pin "J2_4") (pinfunction "SENSOR_VN_J2_4") (pintype "bidirectional"))
    )
    (net (code "205") (name "unconnected-(U1-SENSOR_VP-PadJ2_3)") (class "Default")
      (node (ref "U1") (pin "J2_3") (pinfunction "SENSOR_VP_J2_3") (pintype "bidirectional"))
    )
    (net (code "206") (name "unconnected-(U1-TXD0-PadJ3_4)") (class "Default")
      (node (ref "U1") (pin "J3_4") (pinfunction "TXD0_J3_4") (pintype "bidirectional"))
    )
    (net (code "207") (name "unconnected-(U10-SQH-Pad9)") (class "Default")
      (node (ref "U10") (pin "9") (pinfunction "SQH_9") (pintype "output"))
    )
  )
)
